# Voeding.net
KiCad netlist of a schematic drawn in Altium Designer
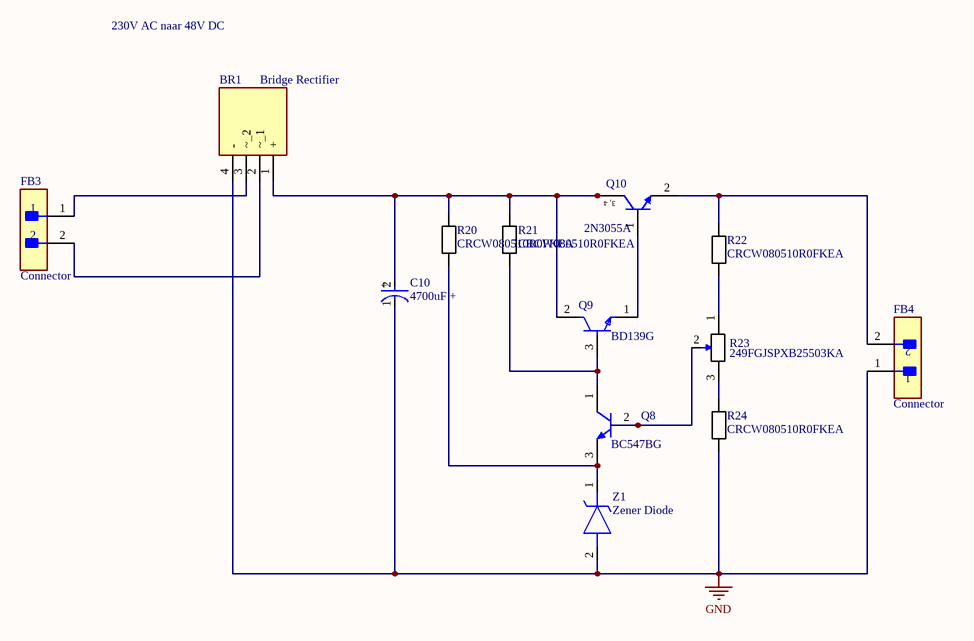
[diagram p0: Voeding.SchDoc]

(export (version "E")
  (design (tool "Eeschema 10.0.6"))
  (components
    (comp (ref "BR1")
      (value "Bridge Rectifier")
      (footprint "Voeding:GBU4KE351")
      (fields
        (field (name "MANUFACTURER_PART_NUMBER") "GBU4K-E3/51")
        (field (name "MOUSER PART NUMBER") "625-GBU4K-E3/51")
      )
      (libsource (lib "Voeding") (part "GBU4K-E3_51"))
    )
    (comp (ref "C10")
      (value "4700uF +")
      (footprint "Elco 4700uF")
      (libsource (lib "Voeding") (part "Elco 4700uF"))
    )
    (comp (ref "FB3")
      (value "Connector")
      (footprint "AB-Amplifier:Connector")
      (description "Ferrite Bead")
      (fields
        (field (name "MANUFACTURER_PART_NUMBER") "ACML-0805-500-T")
        (field (name "MOUSER PART NUMBER") "815-ACML-0805-500T")
      )
      (libsource (lib "") (part "Connector_1"))
    )
    (comp (ref "FB4")
      (value "Connector")
      (footprint "AB-Amplifier:Connector")
      (description "Ferrite Bead")
      (fields
        (field (name "MANUFACTURER_PART_NUMBER") "ACML-0805-500-T")
        (field (name "MOUSER PART NUMBER") "815-ACML-0805-500T")
      )
      (libsource (lib "AB-Amplifier") (part "Connector"))
    )
    (comp (ref "Q8")
      (value "BC547BG")
      (footprint "BC547")
      (description "Amplifier Transistor, NPN Silicon, 3-Pin TO-92, Pb-Free, Bulk Box")
      (fields (field (name "MANUFACTURER") "On Semiconductor"))
      (libsource (lib "Voeding") (part "Transistor - BC547"))
    )
    (comp (ref "Q9")
      (value "BD139G")
      (footprint "BD139")
      (libsource (lib "Voeding") (part "Transistor - BD139"))
    )
    (comp (ref "Q10")
      (value "2N3055A")
      (footprint "2N3055")
      (description "Complementary Silicon High-Power Transistor, 3-Pin TO-204, Tray")
      (fields (field (name "MANUFACTURER") "On Semiconductor"))
      (libsource (lib "Voeding") (part "2N3055"))
    )
    (comp (ref "R20")
      (value "CRCW080510R0FKEA")
      (footprint "0805")
      (fields (field (name "MANUFACTURER") "Vishay Dale"))
      (libsource (lib "Voeding") (part "Resistor 0805"))
    )
    (comp (ref "R21")
      (value "CRCW080510R0FKEA")
      (footprint "0805")
      (fields (field (name "MANUFACTURER") "Vishay Dale"))
      (libsource (lib "Voeding") (part "Resistor 0805"))
    )
    (comp (ref "R22")
      (value "CRCW080510R0FKEA")
      (footprint "0805")
      (fields (field (name "MANUFACTURER") "Vishay Dale"))
      (libsource (lib "Voeding") (part "Resistor 0805"))
    )
    (comp (ref "R23")
      (value "249FGJSPXB25503KA")
      (footprint "Potentiometer 15mm")
      (fields (field (name "TOLERANCE") "10%"))
      (libsource (lib "AB-Amplifier") (part "Potentiometer"))
    )
    (comp (ref "R24")
      (value "CRCW080510R0FKEA")
      (footprint "0805")
      (fields (field (name "MANUFACTURER") "Vishay Dale"))
      (libsource (lib "Voeding") (part "Resistor 0805"))
    )
    (comp (ref "Z1")
      (value "Zener Diode")
      (footprint "Voeding:Zener Diode")
      (fields
        (field (name "MANUFACTURER_PART_NUMBER") "MMSZ5245B-7-F")
        (field (name "MOUSER PART NUMBER") "621-MMSZ5245B-F")
      )
      (libsource (lib "Voeding") (part "Zener Diode"))
    )
  )
  (nets
    (net (code "1") (name "GND") (class "Default")
      (node (ref "BR1") (pin "4") (pinfunction "-_4") (pintype "passive"))
      (node (ref "C10") (pin "1") (pinfunction "C_1") (pintype "passive"))
      (node (ref "FB4") (pin "1") (pinfunction "1_1") (pintype "passive"))
      (node (ref "R24") (pin "1") (pinfunction "1_1") (pintype "passive"))
      (node (ref "Z1") (pin "2") (pinfunction "A_2") (pintype "passive"))
    )
    (net (code "2") (name "Net-(BR1-+)") (class "Default")
      (node (ref "BR1") (pin "1") (pinfunction "+_1") (pintype "passive"))
      (node (ref "C10") (pin "2") (pinfunction "A_2") (pintype "passive"))
      (node (ref "Q10") (pin "3") (pinfunction "C_3") (pintype "passive"))
      (node (ref "Q10") (pin "4") (pinfunction "C_4") (pintype "passive"))
      (node (ref "Q9") (pin "2") (pinfunction "C_2") (pintype "passive"))
      (node (ref "R20") (pin "2") (pinfunction "2_2") (pintype "passive"))
      (node (ref "R21") (pin "2") (pinfunction "2_2") (pintype "passive"))
    )
    (net (code "3") (name "Net-(BR1-~_1)") (class "Default")
      (node (ref "BR1") (pin "2") (pinfunction "~_1_2") (pintype "passive"))
      (node (ref "FB3") (pin "2") (pinfunction "2_2") (pintype "passive"))
    )
    (net (code "4") (name "Net-(BR1-~_2)") (class "Default")
      (node (ref "BR1") (pin "3") (pinfunction "~_2_3") (pintype "passive"))
      (node (ref "FB3") (pin "1") (pinfunction "1_1") (pintype "passive"))
    )
    (net (code "5") (name "Net-(Q8-B)") (class "Default")
      (node (ref "Q8") (pin "2") (pinfunction "B_2") (pintype "passive"))
      (node (ref "R23") (pin "2") (pintype "passive"))
    )
    (net (code "6") (name "Net-(Q8-C)") (class "Default")
      (node (ref "Q8") (pin "1") (pinfunction "C_1") (pintype "passive"))
      (node (ref "Q9") (pin "3") (pinfunction "B_3") (pintype "passive"))
      (node (ref "R21") (pin "1") (pinfunction "1_1") (pintype "passive"))
    )
    (net (code "7") (name "Net-(Q8-E)") (class "Default")
      (node (ref "Q8") (pin "3") (pinfunction "E_3") (pintype "passive"))
      (node (ref "R20") (pin "1") (pinfunction "1_1") (pintype "passive"))
      (node (ref "Z1") (pin "1") (pinfunction "K_1") (pintype "passive"))
    )
    (net (code "8") (name "Net-(Q10-B)") (class "Default")
      (node (ref "Q10") (pin "1") (pinfunction "B_1") (pintype "passive"))
      (node (ref "Q9") (pin "1") (pinfunction "E_1") (pintype "passive"))
    )
    (net (code "9") (name "Net-(Q10-E)") (class "Default")
      (node (ref "FB4") (pin "2") (pinfunction "2_2") (pintype "passive"))
      (node (ref "Q10") (pin "2") (pinfunction "E_2") (pintype "passive"))
      (node (ref "R22") (pin "2") (pinfunction "2_2") (pintype "passive"))
    )
    (net (code "10") (name "Net-(R22-Pad1)") (class "Default")
      (node (ref "R22") (pin "1") (pinfunction "1_1") (pintype "passive"))
      (node (ref "R23") (pin "1") (pinfunction "1_1") (pintype "passive"))
    )
    (net (code "11") (name "Net-(R23-Pad3)") (class "Default")
      (node (ref "R23") (pin "3") (pinfunction "3_3") (pintype "passive"))
      (node (ref "R24") (pin "2") (pinfunction "2_2") (pintype "passive"))
    )
  )
)
